# DBMSch.net
KiCad netlist of a schematic drawn in Altium Designer
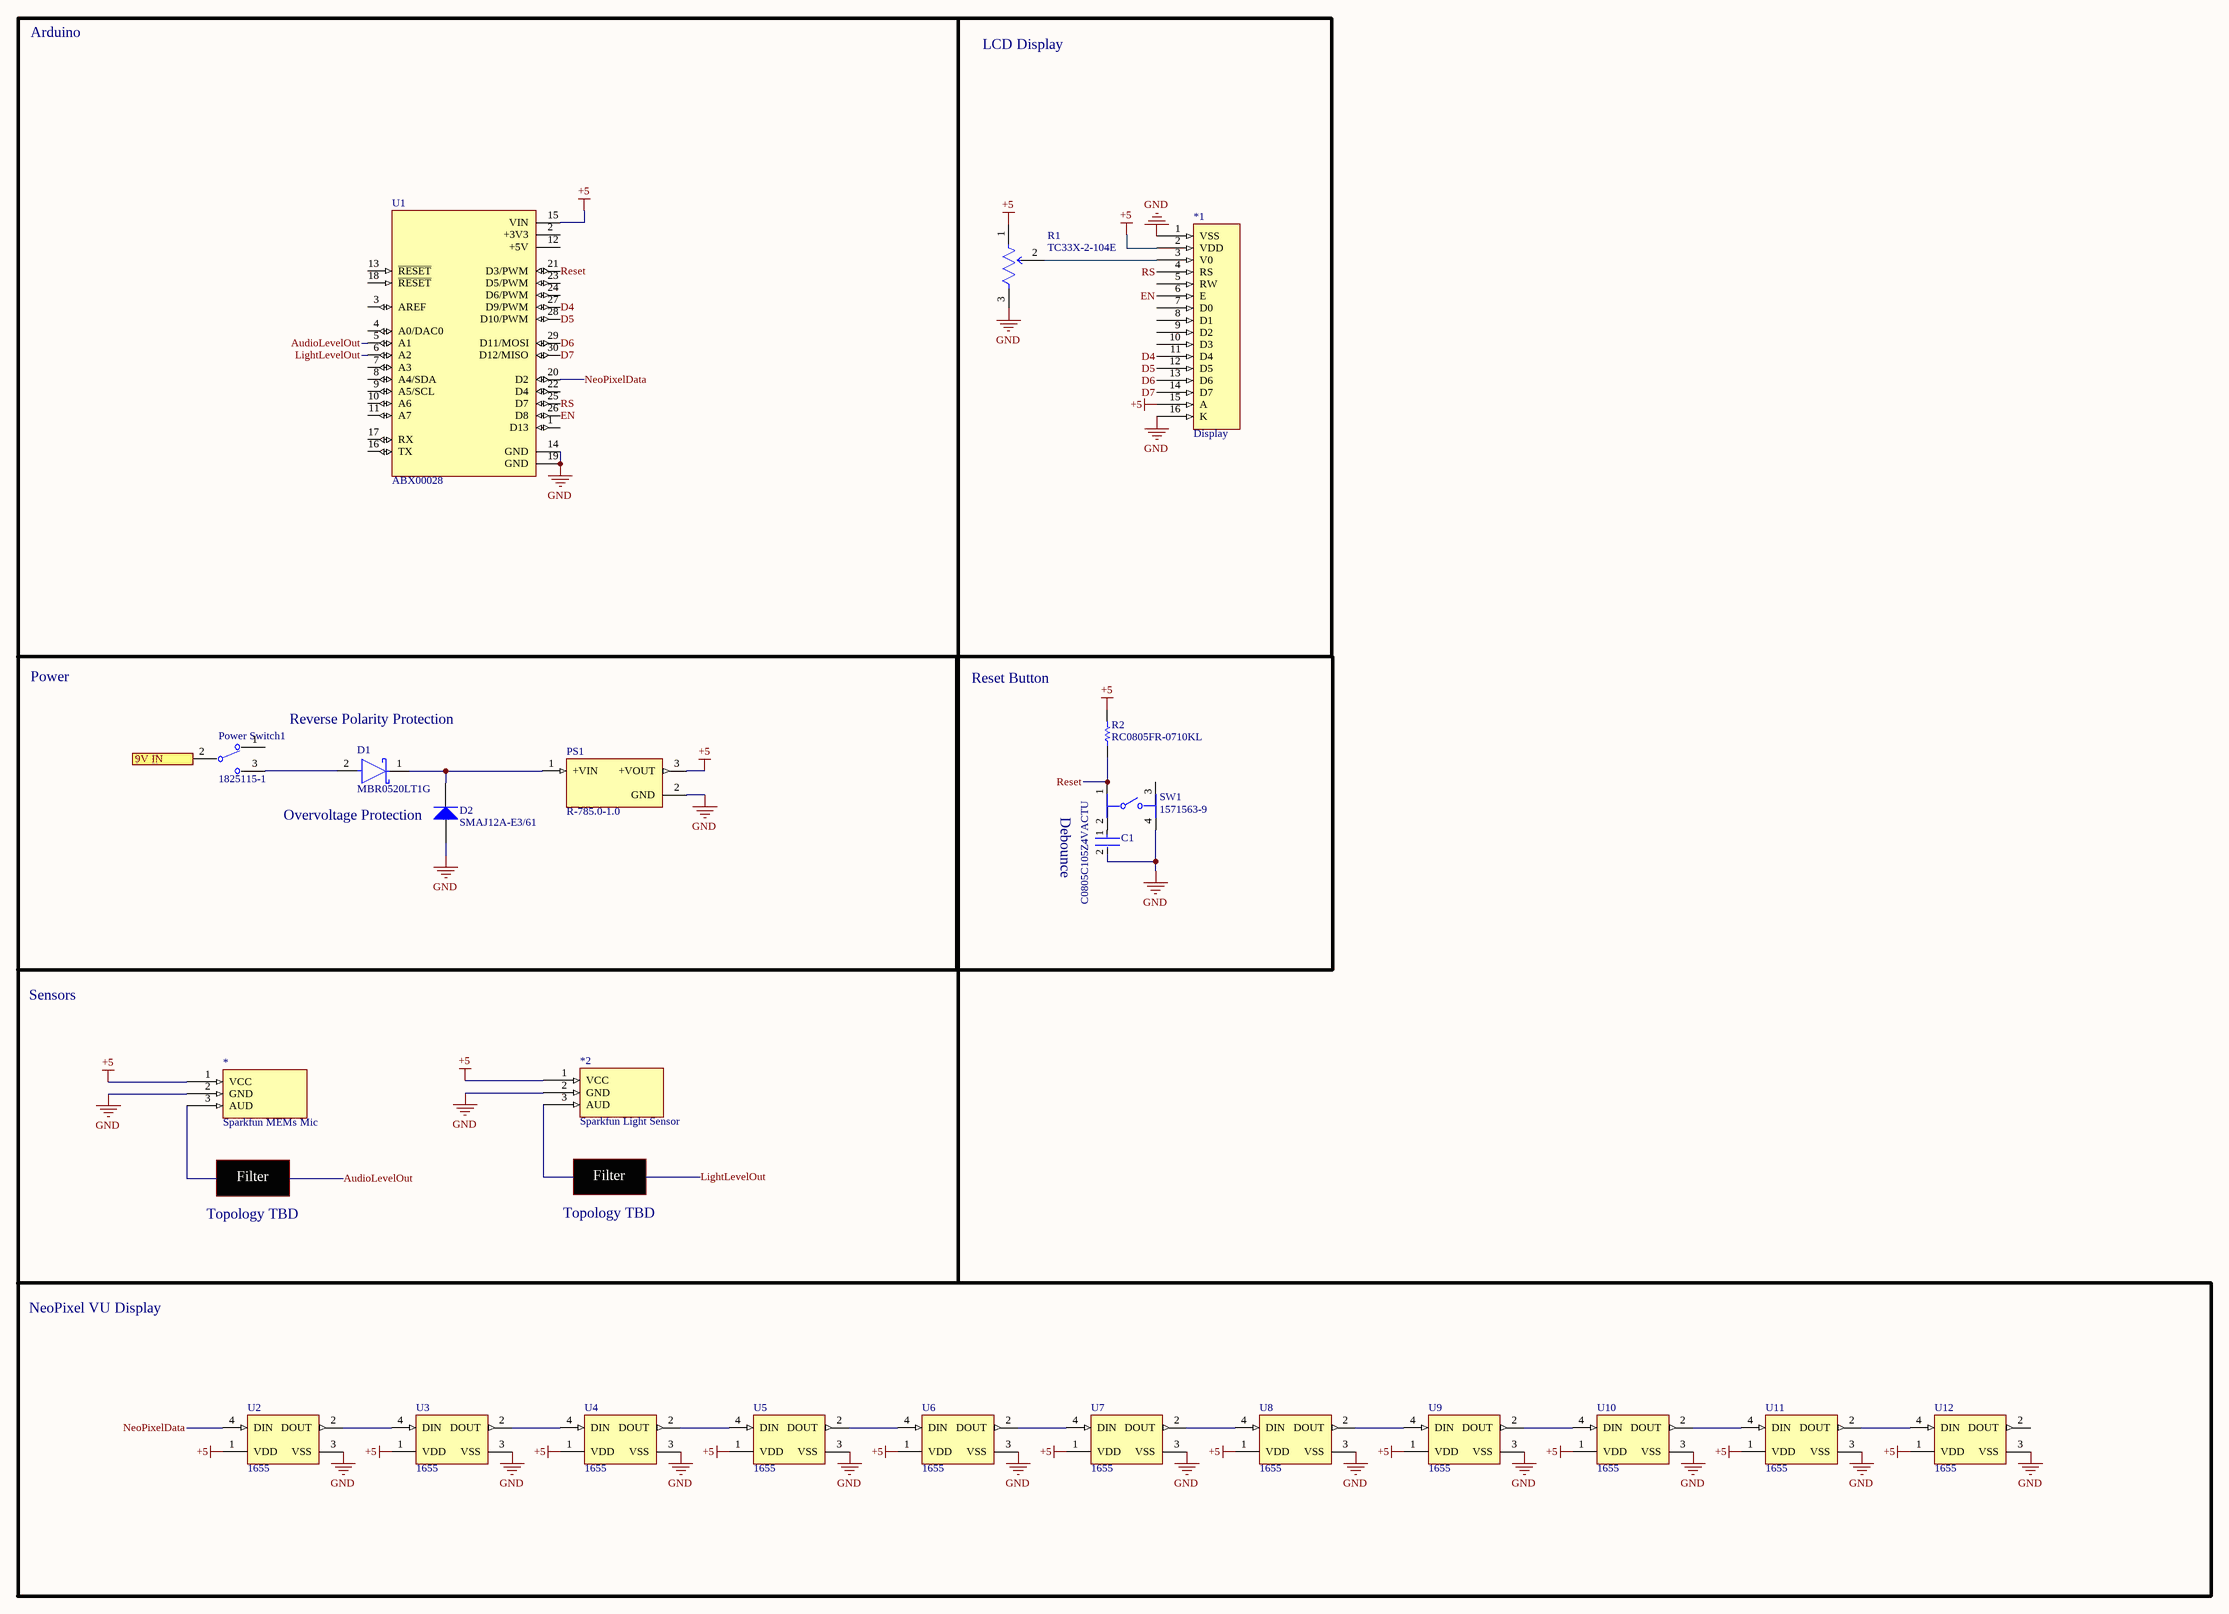
[diagram p0: DBMSch.SchDoc]

(export (version "E")
  (design (tool "Eeschema 10.0.6"))
  (components
    (comp (ref "*") (value "Sparkfun MEMs Mic") (libsource (lib "DBM") (part "Sparkfun MEMs Mic")))
    (comp (ref "*1")
      (value "Display")
      (footprint "Screen Header")
      (libsource (lib "RiceCookerLib") (part "Display"))
    )
    (comp (ref "*2") (value "Sparkfun Light Sensor") (libsource (lib "DBM") (part "Sparkfun MEMs Mic")))
    (comp (ref "C1")
      (value "C0805C105Z4VACTU")
      (footprint "FP-C0805C105Z4VACTU-MFG")
      (description "CAP CER 1UF 16V Y5V 0805")
      (fields (field (name "VOLTAGE") "16V") (field (name "TOLERANCE") "80%"))
      (libsource (lib "Altium Content Vault") (part "02cd4be3c70576c341d710602a673aa"))
    )
    (comp (ref "D1")
      (value "MBR0520LT1G")
      (footprint "FP-425-04-IPC_C")
      (description "DIODE SCHOTTKY 20V 500MA SOD123")
      (libsource (lib "Altium Content Vault") (part "1d6ec82d83fb6aee721767c19dac4b9"))
    )
    (comp (ref "D2")
      (value "SMAJ12A-E3/61")
      (footprint "VISH-DO-214AC-2_N")
      (fields (field (name "MANUFACTURER") "Vishay Semiconductor"))
      (libsource (lib "Altium Content Vault") (part "VISH-K1A2-2"))
    )
    (comp (ref "Power Switch1")
      (value "1825115-1")
      (footprint "FP-1825115-1-MFG")
      (description "Slide Switch SPDT Through Hole")
      (fields (field (name "MANUFACTURER") "TE Connectivity"))
      (libsource (lib "Altium Content Vault") (part "ec4e4964ed0d2d669af15d5af94fda9"))
    )
    (comp (ref "PS1")
      (value "R-785.0-1.0")
      (footprint "R-785.0-1.0:CONV_R-785.0-1.0")
      (description "1.0 Amp SIP3 Single Output")
      (fields (field (name "MF") "{'manufacturer': u'Recom Power'}"))
      (libsource (lib "*") (part "R-785.0-1.0"))
    )
    (comp (ref "R1")
      (value "TC33X-2-104E")
      (footprint "FP-TC33X-2-MFG")
      (description "TRIMMER 100K OHM 0.1W J LEAD TOP")
      (fields (field (name "TOLERANCE") "25%"))
      (libsource (lib "Altium Content Vault") (part "13357d81287629c2fd191d242cfa50c"))
    )
    (comp (ref "R2")
      (value "RC0805FR-0710KL")
      (footprint "RESC2013X60X35NL10T20")
      (description "Chip Resistor, 10 KOhm, +/- 1%, 0.125 W, -55 to 155 degC, 0805 (2012 Metric), RoHS, Tape and Reel")
      (fields (field (name "MANUFACTURER") "Yageo"))
      (libsource (lib "Altium Content Vault") (part "RES-2"))
    )
    (comp (ref "SW1")
      (value "1571563-9")
      (footprint "FP-1571563-9-MFG")
      (description "SWITCH TACTILE SPST-NO 0.05A 24V")
      (fields
        (field (name "MANUFACTURER") "TE Connectivity")
        (field (name "OCTOPART") "https://octopart.com/1571563-9-te+connectivity-41253969")
      )
      (libsource (lib "Altium Content Vault") (part "b8895f3f4cefb76e1819d2863dba89b"))
    )
    (comp (ref "U1")
      (value "ABX00028")
      (footprint "Arduino Nano Every:MODULE_ABX00028")
      (description "ATmega4809 Arduino Nano Every AVR AVR MCU 8-Bit Embedded Evaluation Board")
      (fields (field (name "MF") "{'manufacturer': u'Arduino'}"))
      (libsource (lib "*") (part "ABX00028"))
    )
    (comp (ref "U2")
      (value "1655")
      (footprint "ADA-RGB-1655_V")
      (fields (field (name "MANUFACTURER") "Adafruit-Industries-LLC"))
      (libsource (lib "Altium Content Vault") (part "ADA-RGB-1655-4"))
    )
    (comp (ref "U3")
      (value "1655")
      (footprint "ADA-RGB-1655_V")
      (fields (field (name "MANUFACTURER") "Adafruit-Industries-LLC"))
      (libsource (lib "Altium Content Vault") (part "ADA-RGB-1655-4"))
    )
    (comp (ref "U4")
      (value "1655")
      (footprint "ADA-RGB-1655_V")
      (fields (field (name "MANUFACTURER") "Adafruit-Industries-LLC"))
      (libsource (lib "Altium Content Vault") (part "ADA-RGB-1655-4"))
    )
    (comp (ref "U5")
      (value "1655")
      (footprint "ADA-RGB-1655_V")
      (fields (field (name "MANUFACTURER") "Adafruit-Industries-LLC"))
      (libsource (lib "Altium Content Vault") (part "ADA-RGB-1655-4"))
    )
    (comp (ref "U6")
      (value "1655")
      (footprint "ADA-RGB-1655_V")
      (fields (field (name "MANUFACTURER") "Adafruit-Industries-LLC"))
      (libsource (lib "Altium Content Vault") (part "ADA-RGB-1655-4"))
    )
    (comp (ref "U7")
      (value "1655")
      (footprint "ADA-RGB-1655_V")
      (fields (field (name "MANUFACTURER") "Adafruit-Industries-LLC"))
      (libsource (lib "Altium Content Vault") (part "ADA-RGB-1655-4"))
    )
    (comp (ref "U8")
      (value "1655")
      (footprint "ADA-RGB-1655_V")
      (fields (field (name "MANUFACTURER") "Adafruit-Industries-LLC"))
      (libsource (lib "Altium Content Vault") (part "ADA-RGB-1655-4"))
    )
    (comp (ref "U9")
      (value "1655")
      (footprint "ADA-RGB-1655_V")
      (fields (field (name "MANUFACTURER") "Adafruit-Industries-LLC"))
      (libsource (lib "Altium Content Vault") (part "ADA-RGB-1655-4"))
    )
    (comp (ref "U10")
      (value "1655")
      (footprint "ADA-RGB-1655_V")
      (fields (field (name "MANUFACTURER") "Adafruit-Industries-LLC"))
      (libsource (lib "Altium Content Vault") (part "ADA-RGB-1655-4"))
    )
    (comp (ref "U11")
      (value "1655")
      (footprint "ADA-RGB-1655_V")
      (fields (field (name "MANUFACTURER") "Adafruit-Industries-LLC"))
      (libsource (lib "Altium Content Vault") (part "ADA-RGB-1655-4"))
    )
    (comp (ref "U12")
      (value "1655")
      (footprint "ADA-RGB-1655_V")
      (fields (field (name "MANUFACTURER") "Adafruit-Industries-LLC"))
      (libsource (lib "Altium Content Vault") (part "ADA-RGB-1655-4"))
    )
  )
  (nets
    (net (code "1") (name "+5") (class "Default")
      (node (ref "*") (pin "1") (pinfunction "VCC_1") (pintype "input"))
      (node (ref "*1") (pin "15") (pinfunction "A_15") (pintype "input"))
      (node (ref "*1") (pin "2") (pinfunction "VDD_2") (pintype "input"))
      (node (ref "*2") (pin "1") (pinfunction "VCC_1") (pintype "input"))
      (node (ref "PS1") (pin "3") (pinfunction "+VOUT_3") (pintype "output"))
      (node (ref "R1") (pin "1") (pinfunction "CCW_1") (pintype "passive"))
      (node (ref "R2") (pin "2") (pinfunction "2_2") (pintype "passive"))
      (node (ref "U1") (pin "15") (pinfunction "VIN_15") (pintype "power_in"))
      (node (ref "U10") (pin "1") (pinfunction "VDD_1") (pintype "power_in"))
      (node (ref "U11") (pin "1") (pinfunction "VDD_1") (pintype "power_in"))
      (node (ref "U12") (pin "1") (pinfunction "VDD_1") (pintype "power_in"))
      (node (ref "U2") (pin "1") (pinfunction "VDD_1") (pintype "power_in"))
      (node (ref "U3") (pin "1") (pinfunction "VDD_1") (pintype "power_in"))
      (node (ref "U4") (pin "1") (pinfunction "VDD_1") (pintype "power_in"))
      (node (ref "U5") (pin "1") (pinfunction "VDD_1") (pintype "power_in"))
      (node (ref "U6") (pin "1") (pinfunction "VDD_1") (pintype "power_in"))
      (node (ref "U7") (pin "1") (pinfunction "VDD_1") (pintype "power_in"))
      (node (ref "U8") (pin "1") (pinfunction "VDD_1") (pintype "power_in"))
      (node (ref "U9") (pin "1") (pinfunction "VDD_1") (pintype "power_in"))
    )
    (net (code "2") (name "/9V IN") (class "Default")
      (node (ref "Power Switch1") (pin "2") (pinfunction "2_2") (pintype "passive"))
    )
    (net (code "3") (name "/AudioLevelOut") (class "Default")
      (node (ref "U1") (pin "5") (pinfunction "A1_5") (pintype "bidirectional"))
    )
    (net (code "4") (name "/D4") (class "Default")
      (node (ref "*1") (pin "11") (pinfunction "D4_11") (pintype "input"))
      (node (ref "U1") (pin "27") (pinfunction "D9/PWM_27") (pintype "bidirectional"))
    )
    (net (code "5") (name "/D5") (class "Default")
      (node (ref "*1") (pin "12") (pinfunction "D5_12") (pintype "input"))
      (node (ref "U1") (pin "28") (pinfunction "D10/PWM_28") (pintype "bidirectional"))
    )
    (net (code "6") (name "/D6") (class "Default")
      (node (ref "*1") (pin "13") (pinfunction "D6_13") (pintype "input"))
      (node (ref "U1") (pin "29") (pinfunction "D11/MOSI_29") (pintype "bidirectional"))
    )
    (net (code "7") (name "/D7") (class "Default")
      (node (ref "*1") (pin "14") (pinfunction "D7_14") (pintype "input"))
      (node (ref "U1") (pin "30") (pinfunction "D12/MISO_30") (pintype "bidirectional"))
    )
    (net (code "8") (name "/EN") (class "Default")
      (node (ref "*1") (pin "6") (pinfunction "E_6") (pintype "input"))
      (node (ref "U1") (pin "26") (pinfunction "D8_26") (pintype "bidirectional"))
    )
    (net (code "9") (name "/LightLevelOut") (class "Default")
      (node (ref "U1") (pin "6") (pinfunction "A2_6") (pintype "bidirectional"))
    )
    (net (code "10") (name "/NeoPixelData") (class "Default")
      (node (ref "U1") (pin "20") (pinfunction "D2_20") (pintype "bidirectional"))
      (node (ref "U2") (pin "4") (pinfunction "DIN_4") (pintype "input"))
    )
    (net (code "11") (name "/RS") (class "Default")
      (node (ref "*1") (pin "4") (pinfunction "RS_4") (pintype "input"))
      (node (ref "U1") (pin "25") (pinfunction "D7_25") (pintype "bidirectional"))
    )
    (net (code "12") (name "/Reset") (class "Default")
      (node (ref "R2") (pin "1") (pinfunction "1_1") (pintype "passive"))
      (node (ref "SW1") (pin "1") (pinfunction "1_1") (pintype "passive"))
      (node (ref "U1") (pin "21") (pinfunction "D3/PWM_21") (pintype "bidirectional"))
    )
    (net (code "13") (name "GND") (class "Default")
      (node (ref "*") (pin "2") (pinfunction "GND_2") (pintype "input"))
      (node (ref "*1") (pin "1") (pinfunction "VSS_1") (pintype "input"))
      (node (ref "*1") (pin "16") (pinfunction "K_16") (pintype "input"))
      (node (ref "*2") (pin "2") (pinfunction "GND_2") (pintype "input"))
      (node (ref "C1") (pin "2") (pinfunction "2_2") (pintype "passive"))
      (node (ref "D2") (pin "2") (pinfunction "A_2") (pintype "passive"))
      (node (ref "PS1") (pin "2") (pinfunction "GND_2") (pintype "power_in"))
      (node (ref "R1") (pin "3") (pinfunction "CW_3") (pintype "passive"))
      (node (ref "SW1") (pin "4") (pinfunction "4_4") (pintype "passive"))
      (node (ref "U1") (pin "14") (pinfunction "GND_14") (pintype "power_in"))
      (node (ref "U1") (pin "19") (pinfunction "GND_19") (pintype "power_in"))
      (node (ref "U10") (pin "3") (pinfunction "VSS_3") (pintype "power_in"))
      (node (ref "U11") (pin "3") (pinfunction "VSS_3") (pintype "power_in"))
      (node (ref "U12") (pin "3") (pinfunction "VSS_3") (pintype "power_in"))
      (node (ref "U2") (pin "3") (pinfunction "VSS_3") (pintype "power_in"))
      (node (ref "U3") (pin "3") (pinfunction "VSS_3") (pintype "power_in"))
      (node (ref "U4") (pin "3") (pinfunction "VSS_3") (pintype "power_in"))
      (node (ref "U5") (pin "3") (pinfunction "VSS_3") (pintype "power_in"))
      (node (ref "U6") (pin "3") (pinfunction "VSS_3") (pintype "power_in"))
      (node (ref "U7") (pin "3") (pinfunction "VSS_3") (pintype "power_in"))
      (node (ref "U8") (pin "3") (pinfunction "VSS_3") (pintype "power_in"))
      (node (ref "U9") (pin "3") (pinfunction "VSS_3") (pintype "power_in"))
    )
    (net (code "14") (name "Net-(*1-V0)") (class "Default")
      (node (ref "*1") (pin "3") (pinfunction "V0_3") (pintype "input"))
      (node (ref "R1") (pin "2") (pinfunction "WIPER_2") (pintype "passive"))
    )
    (net (code "15") (name "Net-(C1-Pad1)") (class "Default")
      (node (ref "C1") (pin "1") (pinfunction "1_1") (pintype "passive"))
      (node (ref "SW1") (pin "2") (pinfunction "2_2") (pintype "passive"))
    )
    (net (code "16") (name "Net-(D1-A)") (class "Default")
      (node (ref "D1") (pin "2") (pinfunction "A_2") (pintype "passive"))
      (node (ref "Power Switch1") (pin "3") (pinfunction "3_3") (pintype "passive"))
    )
    (net (code "17") (name "Net-(D1-C)") (class "Default")
      (node (ref "D1") (pin "1") (pinfunction "C_1") (pintype "passive"))
      (node (ref "D2") (pin "1") (pinfunction "K_1") (pintype "passive"))
      (node (ref "PS1") (pin "1") (pinfunction "+VIN_1") (pintype "input"))
    )
    (net (code "18") (name "Net-(U2-DOUT)") (class "Default")
      (node (ref "U2") (pin "2") (pinfunction "DOUT_2") (pintype "output"))
      (node (ref "U3") (pin "4") (pinfunction "DIN_4") (pintype "input"))
    )
    (net (code "19") (name "Net-(U3-DOUT)") (class "Default")
      (node (ref "U3") (pin "2") (pinfunction "DOUT_2") (pintype "output"))
      (node (ref "U4") (pin "4") (pinfunction "DIN_4") (pintype "input"))
    )
    (net (code "20") (name "Net-(U4-DOUT)") (class "Default")
      (node (ref "U4") (pin "2") (pinfunction "DOUT_2") (pintype "output"))
      (node (ref "U5") (pin "4") (pinfunction "DIN_4") (pintype "input"))
    )
    (net (code "21") (name "Net-(U5-DOUT)") (class "Default")
      (node (ref "U5") (pin "2") (pinfunction "DOUT_2") (pintype "output"))
      (node (ref "U6") (pin "4") (pinfunction "DIN_4") (pintype "input"))
    )
    (net (code "22") (name "Net-(U6-DOUT)") (class "Default")
      (node (ref "U6") (pin "2") (pinfunction "DOUT_2") (pintype "output"))
      (node (ref "U7") (pin "4") (pinfunction "DIN_4") (pintype "input"))
    )
    (net (code "23") (name "Net-(U7-DOUT)") (class "Default")
      (node (ref "U7") (pin "2") (pinfunction "DOUT_2") (pintype "output"))
      (node (ref "U8") (pin "4") (pinfunction "DIN_4") (pintype "input"))
    )
    (net (code "24") (name "Net-(U8-DOUT)") (class "Default")
      (node (ref "U8") (pin "2") (pinfunction "DOUT_2") (pintype "output"))
      (node (ref "U9") (pin "4") (pinfunction "DIN_4") (pintype "input"))
    )
    (net (code "25") (name "Net-(U10-DIN)") (class "Default")
      (node (ref "U10") (pin "4") (pinfunction "DIN_4") (pintype "input"))
      (node (ref "U9") (pin "2") (pinfunction "DOUT_2") (pintype "output"))
    )
    (net (code "26") (name "Net-(U10-DOUT)") (class "Default")
      (node (ref "U10") (pin "2") (pinfunction "DOUT_2") (pintype "output"))
      (node (ref "U11") (pin "4") (pinfunction "DIN_4") (pintype "input"))
    )
    (net (code "27") (name "Net-(U11-DOUT)") (class "Default")
      (node (ref "U11") (pin "2") (pinfunction "DOUT_2") (pintype "output"))
      (node (ref "U12") (pin "4") (pinfunction "DIN_4") (pintype "input"))
    )
    (net (code "28") (name "unconnected-(*-AUD-Pad3)") (class "Default")
      (node (ref "*") (pin "3") (pinfunction "AUD_3") (pintype "input"))
    )
    (net (code "29") (name "unconnected-(*1-D0-Pad7)") (class "Default")
      (node (ref "*1") (pin "7") (pinfunction "D0_7") (pintype "input"))
    )
    (net (code "30") (name "unconnected-(*1-D1-Pad8)") (class "Default")
      (node (ref "*1") (pin "8") (pinfunction "D1_8") (pintype "input"))
    )
    (net (code "31") (name "unconnected-(*1-D2-Pad9)") (class "Default")
      (node (ref "*1") (pin "9") (pinfunction "D2_9") (pintype "input"))
    )
    (net (code "32") (name "unconnected-(*1-D3-Pad10)") (class "Default")
      (node (ref "*1") (pin "10") (pinfunction "D3_10") (pintype "input"))
    )
    (net (code "33") (name "unconnected-(*1-RW-Pad5)") (class "Default")
      (node (ref "*1") (pin "5") (pinfunction "RW_5") (pintype "input"))
    )
    (net (code "34") (name "unconnected-(*2-AUD-Pad3)") (class "Default")
      (node (ref "*2") (pin "3") (pinfunction "AUD_3") (pintype "input"))
    )
    (net (code "35") (name "unconnected-(Power Switch1-Pad1)") (class "Default")
      (node (ref "Power Switch1") (pin "1") (pinfunction "1_1") (pintype "passive"))
    )
    (net (code "36") (name "unconnected-(SW1-Pad3)") (class "Default")
      (node (ref "SW1") (pin "3") (pinfunction "3_3") (pintype "passive"))
    )
    (net (code "37") (name "unconnected-(U1-+3V3-Pad2)") (class "Default")
      (node (ref "U1") (pin "2") (pinfunction "+3V3_2") (pintype "power_in"))
    )
    (net (code "38") (name "unconnected-(U1-+5V-Pad12)") (class "Default")
      (node (ref "U1") (pin "12") (pinfunction "+5V_12") (pintype "power_in"))
    )
    (net (code "39") (name "unconnected-(U1-A0{slash}DAC0-Pad4)") (class "Default")
      (node (ref "U1") (pin "4") (pinfunction "A0/DAC0_4") (pintype "bidirectional"))
    )
    (net (code "40") (name "unconnected-(U1-A3-Pad7)") (class "Default")
      (node (ref "U1") (pin "7") (pinfunction "A3_7") (pintype "bidirectional"))
    )
    (net (code "41") (name "unconnected-(U1-A4{slash}SDA-Pad8)") (class "Default")
      (node (ref "U1") (pin "8") (pinfunction "A4/SDA_8") (pintype "bidirectional"))
    )
    (net (code "42") (name "unconnected-(U1-A5{slash}SCL-Pad9)") (class "Default")
      (node (ref "U1") (pin "9") (pinfunction "A5/SCL_9") (pintype "bidirectional"))
    )
    (net (code "43") (name "unconnected-(U1-A6-Pad10)") (class "Default")
      (node (ref "U1") (pin "10") (pinfunction "A6_10") (pintype "bidirectional"))
    )
    (net (code "44") (name "unconnected-(U1-A7-Pad11)") (class "Default")
      (node (ref "U1") (pin "11") (pinfunction "A7_11") (pintype "bidirectional"))
    )
    (net (code "45") (name "unconnected-(U1-AREF-Pad3)") (class "Default")
      (node (ref "U1") (pin "3") (pinfunction "AREF_3") (pintype "bidirectional"))
    )
    (net (code "46") (name "unconnected-(U1-D4-Pad22)") (class "Default")
      (node (ref "U1") (pin "22") (pinfunction "D4_22") (pintype "bidirectional"))
    )
    (net (code "47") (name "unconnected-(U1-D5{slash}PWM-Pad23)") (class "Default")
      (node (ref "U1") (pin "23") (pinfunction "D5/PWM_23") (pintype "bidirectional"))
    )
    (net (code "48") (name "unconnected-(U1-D6{slash}PWM-Pad24)") (class "Default")
      (node (ref "U1") (pin "24") (pinfunction "D6/PWM_24") (pintype "bidirectional"))
    )
    (net (code "49") (name "unconnected-(U1-D13-Pad1)") (class "Default")
      (node (ref "U1") (pin "1") (pinfunction "D13_1") (pintype "bidirectional"))
    )
    (net (code "50") (name "unconnected-(U1-RX-Pad17)") (class "Default")
      (node (ref "U1") (pin "17") (pinfunction "RX_17") (pintype "bidirectional"))
    )
    (net (code "51") (name "unconnected-(U1-TX-Pad16)") (class "Default")
      (node (ref "U1") (pin "16") (pinfunction "TX_16") (pintype "bidirectional"))
    )
    (net (code "52") (name "unconnected-(U1-~{RESET}-Pad13)") (class "Default")
      (node (ref "U1") (pin "13") (pinfunction "~{RESET}_13") (pintype "input"))
    )
    (net (code "53") (name "unconnected-(U1-~{RESET}-Pad18)") (class "Default")
      (node (ref "U1") (pin "18") (pinfunction "~{RESET}_18") (pintype "input"))
    )
    (net (code "54") (name "unconnected-(U12-DOUT-Pad2)") (class "Default")
      (node (ref "U12") (pin "2") (pinfunction "DOUT_2") (pintype "output"))
    )
  )
)
